# DC-DC_Filter_Schematic.net
KiCad netlist of a schematic drawn in Altium Designer
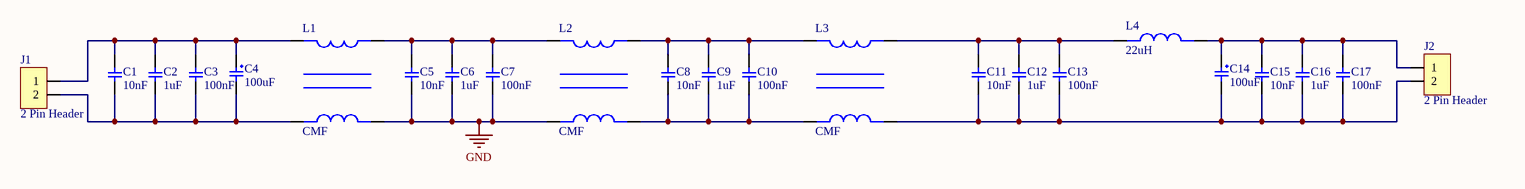
[diagram p0: DC-DC Filter Schematic.SchDoc]

(export (version "E")
  (design (tool "Eeschema 10.0.6"))
  (components
    (comp (ref "C1") (value "10nF") (footprint "CAP805") (libsource (lib "Schlib1") (part "Capacitor")))
    (comp (ref "C2") (value "1uF") (footprint "CAP805") (libsource (lib "Schlib1") (part "Capacitor")))
    (comp (ref "C3") (value "100nF") (footprint "CAP805") (libsource (lib "Schlib1") (part "Capacitor")))
    (comp (ref "C4") (value "100uF") (footprint "V-CHIP CAP") (libsource (lib "Schlib1") (part "Cap pol")))
    (comp (ref "C5") (value "10nF") (footprint "CAP805") (libsource (lib "Schlib1") (part "Capacitor")))
    (comp (ref "C6") (value "1uF") (footprint "CAP805") (libsource (lib "Schlib1") (part "Capacitor")))
    (comp (ref "C7") (value "100nF") (footprint "CAP805") (libsource (lib "Schlib1") (part "Capacitor")))
    (comp (ref "C8") (value "10nF") (footprint "CAP805") (libsource (lib "Schlib1") (part "Capacitor")))
    (comp (ref "C9") (value "1uF") (footprint "CAP805") (libsource (lib "Schlib1") (part "Capacitor")))
    (comp (ref "C10") (value "100nF") (footprint "CAP805") (libsource (lib "Schlib1") (part "Capacitor")))
    (comp (ref "C11") (value "10nF") (footprint "CAP805") (libsource (lib "Schlib1") (part "Capacitor")))
    (comp (ref "C12") (value "1uF") (footprint "CAP805") (libsource (lib "Schlib1") (part "Capacitor")))
    (comp (ref "C13") (value "100nF") (footprint "CAP805") (libsource (lib "Schlib1") (part "Capacitor")))
    (comp (ref "C14") (value "100uF") (footprint "V-CHIP CAP") (libsource (lib "Schlib1") (part "Cap pol")))
    (comp (ref "C15") (value "10nF") (footprint "CAP805") (libsource (lib "Schlib1") (part "Capacitor")))
    (comp (ref "C16") (value "1uF") (footprint "CAP805") (libsource (lib "Schlib1") (part "Capacitor")))
    (comp (ref "C17") (value "100nF") (footprint "CAP805") (libsource (lib "Schlib1") (part "Capacitor")))
    (comp (ref "J1")
      (value "2 Pin Header")
      (footprint "2POS_5.08mm_Terminal")
      (libsource (lib "") (part "2 Pin Header_1"))
    )
    (comp (ref "J2")
      (value "2 Pin Header")
      (footprint "2POS_5.08mm_Terminal")
      (libsource (lib "Schlib1") (part "2 Pin Header"))
    )
    (comp (ref "L1") (value "CMF") (footprint "CMF") (libsource (lib "Schlib1") (part "CMF")))
    (comp (ref "L2") (value "CMF") (footprint "CMF") (libsource (lib "Schlib1") (part "CMF")))
    (comp (ref "L3") (value "CMF") (footprint "CMF") (libsource (lib "Schlib1") (part "CMF")))
    (comp (ref "L4") (value "22uH") (footprint "Inductor") (libsource (lib "Schlib1") (part "Inductor")))
  )
  (nets
    (net (code "1") (name "GND") (class "Default")
      (node (ref "C5") (pin "1") (pinfunction "1_1") (pintype "passive"))
      (node (ref "C6") (pin "1") (pinfunction "1_1") (pintype "passive"))
      (node (ref "C7") (pin "1") (pinfunction "1_1") (pintype "passive"))
      (node (ref "L1") (pin "3") (pinfunction "3_3") (pintype "passive"))
      (node (ref "L2") (pin "2") (pinfunction "2_2") (pintype "passive"))
    )
    (net (code "2") (name "Net-(C1-Pad1)") (class "Default")
      (node (ref "C1") (pin "1") (pinfunction "1_1") (pintype "passive"))
      (node (ref "C2") (pin "1") (pinfunction "1_1") (pintype "passive"))
      (node (ref "C3") (pin "1") (pinfunction "1_1") (pintype "passive"))
      (node (ref "C4") (pin "2") (pinfunction "2_2") (pintype "passive"))
      (node (ref "J1") (pin "2") (pinfunction "2_2") (pintype "passive"))
      (node (ref "L1") (pin "2") (pinfunction "2_2") (pintype "passive"))
    )
    (net (code "3") (name "Net-(C1-Pad2)") (class "Default")
      (node (ref "C1") (pin "2") (pinfunction "2_2") (pintype "passive"))
      (node (ref "C2") (pin "2") (pinfunction "2_2") (pintype "passive"))
      (node (ref "C3") (pin "2") (pinfunction "2_2") (pintype "passive"))
      (node (ref "C4") (pin "1") (pinfunction "1_1") (pintype "passive"))
      (node (ref "J1") (pin "1") (pinfunction "1_1") (pintype "passive"))
      (node (ref "L1") (pin "1") (pinfunction "1_1") (pintype "passive"))
    )
    (net (code "4") (name "Net-(C5-Pad2)") (class "Default")
      (node (ref "C5") (pin "2") (pinfunction "2_2") (pintype "passive"))
      (node (ref "C6") (pin "2") (pinfunction "2_2") (pintype "passive"))
      (node (ref "C7") (pin "2") (pinfunction "2_2") (pintype "passive"))
      (node (ref "L1") (pin "4") (pinfunction "4_4") (pintype "passive"))
      (node (ref "L2") (pin "1") (pinfunction "1_1") (pintype "passive"))
    )
    (net (code "5") (name "Net-(C10-Pad1)") (class "Default")
      (node (ref "C10") (pin "1") (pinfunction "1_1") (pintype "passive"))
      (node (ref "C8") (pin "1") (pinfunction "1_1") (pintype "passive"))
      (node (ref "C9") (pin "1") (pinfunction "1_1") (pintype "passive"))
      (node (ref "L2") (pin "3") (pinfunction "3_3") (pintype "passive"))
      (node (ref "L3") (pin "2") (pinfunction "2_2") (pintype "passive"))
    )
    (net (code "6") (name "Net-(C10-Pad2)") (class "Default")
      (node (ref "C10") (pin "2") (pinfunction "2_2") (pintype "passive"))
      (node (ref "C8") (pin "2") (pinfunction "2_2") (pintype "passive"))
      (node (ref "C9") (pin "2") (pinfunction "2_2") (pintype "passive"))
      (node (ref "L2") (pin "4") (pinfunction "4_4") (pintype "passive"))
      (node (ref "L3") (pin "1") (pinfunction "1_1") (pintype "passive"))
    )
    (net (code "7") (name "Net-(C11-Pad1)") (class "Default")
      (node (ref "C11") (pin "1") (pinfunction "1_1") (pintype "passive"))
      (node (ref "C12") (pin "1") (pinfunction "1_1") (pintype "passive"))
      (node (ref "C13") (pin "1") (pinfunction "1_1") (pintype "passive"))
      (node (ref "C14") (pin "2") (pinfunction "2_2") (pintype "passive"))
      (node (ref "C15") (pin "1") (pinfunction "1_1") (pintype "passive"))
      (node (ref "C16") (pin "1") (pinfunction "1_1") (pintype "passive"))
      (node (ref "C17") (pin "1") (pinfunction "1_1") (pintype "passive"))
      (node (ref "J2") (pin "2") (pinfunction "2_2") (pintype "passive"))
      (node (ref "L3") (pin "3") (pinfunction "3_3") (pintype "passive"))
    )
    (net (code "8") (name "Net-(C11-Pad2)") (class "Default")
      (node (ref "C11") (pin "2") (pinfunction "2_2") (pintype "passive"))
      (node (ref "C12") (pin "2") (pinfunction "2_2") (pintype "passive"))
      (node (ref "C13") (pin "2") (pinfunction "2_2") (pintype "passive"))
      (node (ref "L3") (pin "4") (pinfunction "4_4") (pintype "passive"))
      (node (ref "L4") (pin "1") (pinfunction "1_1") (pintype "passive"))
    )
    (net (code "9") (name "Net-(C14-Pad1)") (class "Default")
      (node (ref "C14") (pin "1") (pinfunction "1_1") (pintype "passive"))
      (node (ref "C15") (pin "2") (pinfunction "2_2") (pintype "passive"))
      (node (ref "C16") (pin "2") (pinfunction "2_2") (pintype "passive"))
      (node (ref "C17") (pin "2") (pinfunction "2_2") (pintype "passive"))
      (node (ref "J2") (pin "1") (pinfunction "1_1") (pintype "passive"))
      (node (ref "L4") (pin "2") (pinfunction "2_2") (pintype "passive"))
    )
  )
)
